# LED_Daughterboard.net
KiCad netlist of a schematic drawn in EAGLE
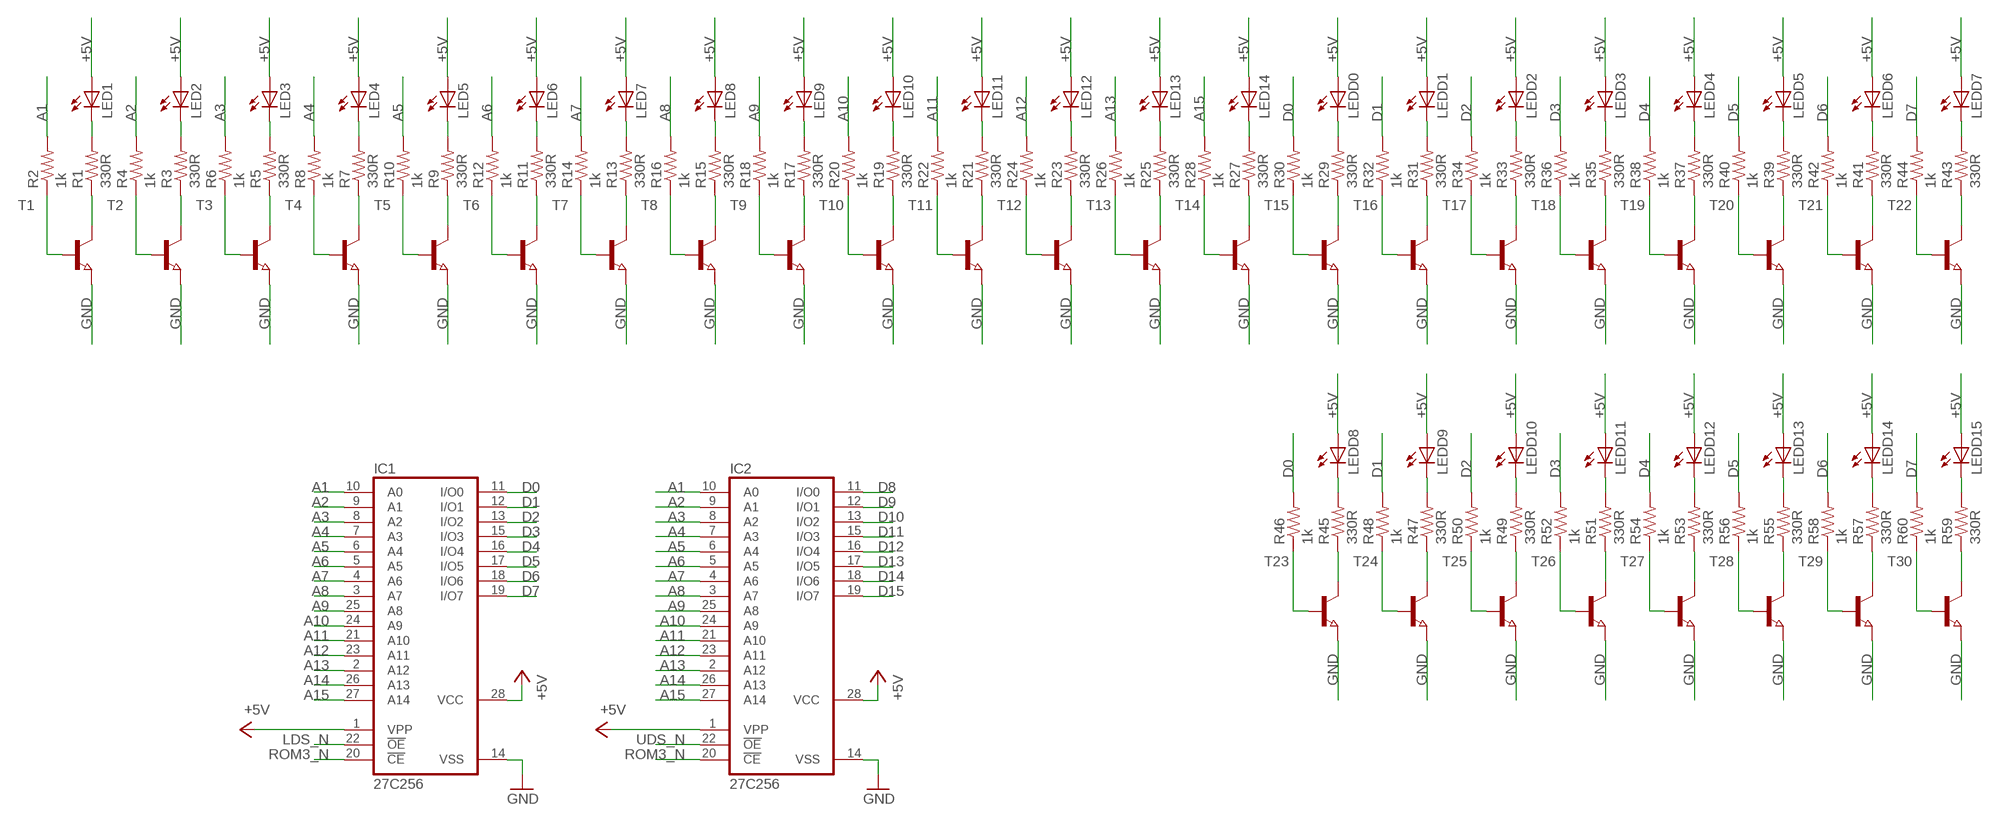
[diagram p0: schematic, sheet 1]

(export (version "E")
  (design (tool "Eeschema 10.0.6"))
  (components
    (comp (ref "IC1")
      (value "27C256")
      (footprint "eagle-import:DIL28-6")
      (libsource (lib "eagle-import") (part "27C256AG"))
    )
    (comp (ref "IC2")
      (value "27C256")
      (footprint "eagle-import:DIL28-6")
      (libsource (lib "eagle-import") (part "27C256AG"))
    )
    (comp (ref "LED1")
      (value "LEDCHIP-LED0805")
      (footprint "eagle-import:CHIP-LED0805")
      (libsource (lib "eagle-import") (part "LEDCHIP-LED0805"))
    )
    (comp (ref "LED2")
      (value "LEDCHIP-LED0805")
      (footprint "eagle-import:CHIP-LED0805")
      (libsource (lib "eagle-import") (part "LEDCHIP-LED0805"))
    )
    (comp (ref "LED3")
      (value "LEDCHIP-LED0805")
      (footprint "eagle-import:CHIP-LED0805")
      (libsource (lib "eagle-import") (part "LEDCHIP-LED0805"))
    )
    (comp (ref "LED4")
      (value "LEDCHIP-LED0805")
      (footprint "eagle-import:CHIP-LED0805")
      (libsource (lib "eagle-import") (part "LEDCHIP-LED0805"))
    )
    (comp (ref "LED5")
      (value "LEDCHIP-LED0805")
      (footprint "eagle-import:CHIP-LED0805")
      (libsource (lib "eagle-import") (part "LEDCHIP-LED0805"))
    )
    (comp (ref "LED6")
      (value "LEDCHIP-LED0805")
      (footprint "eagle-import:CHIP-LED0805")
      (libsource (lib "eagle-import") (part "LEDCHIP-LED0805"))
    )
    (comp (ref "LED7")
      (value "LEDCHIP-LED0805")
      (footprint "eagle-import:CHIP-LED0805")
      (libsource (lib "eagle-import") (part "LEDCHIP-LED0805"))
    )
    (comp (ref "LED8")
      (value "LEDCHIP-LED0805")
      (footprint "eagle-import:CHIP-LED0805")
      (libsource (lib "eagle-import") (part "LEDCHIP-LED0805"))
    )
    (comp (ref "LED9")
      (value "LEDCHIP-LED0805")
      (footprint "eagle-import:CHIP-LED0805")
      (libsource (lib "eagle-import") (part "LEDCHIP-LED0805"))
    )
    (comp (ref "LED10")
      (value "LEDCHIP-LED0805")
      (footprint "eagle-import:CHIP-LED0805")
      (libsource (lib "eagle-import") (part "LEDCHIP-LED0805"))
    )
    (comp (ref "LED11")
      (value "LEDCHIP-LED0805")
      (footprint "eagle-import:CHIP-LED0805")
      (libsource (lib "eagle-import") (part "LEDCHIP-LED0805"))
    )
    (comp (ref "LED12")
      (value "LEDCHIP-LED0805")
      (footprint "eagle-import:CHIP-LED0805")
      (libsource (lib "eagle-import") (part "LEDCHIP-LED0805"))
    )
    (comp (ref "LED13")
      (value "LEDCHIP-LED0805")
      (footprint "eagle-import:CHIP-LED0805")
      (libsource (lib "eagle-import") (part "LEDCHIP-LED0805"))
    )
    (comp (ref "LED14")
      (value "LEDCHIP-LED0805")
      (footprint "eagle-import:CHIP-LED0805")
      (libsource (lib "eagle-import") (part "LEDCHIP-LED0805"))
    )
    (comp (ref "LEDD0")
      (value "LEDCHIP-LED0805")
      (footprint "eagle-import:CHIP-LED0805")
      (libsource (lib "eagle-import") (part "LEDCHIP-LED0805"))
    )
    (comp (ref "LEDD1")
      (value "LEDCHIP-LED0805")
      (footprint "eagle-import:CHIP-LED0805")
      (libsource (lib "eagle-import") (part "LEDCHIP-LED0805"))
    )
    (comp (ref "LEDD2")
      (value "LEDCHIP-LED0805")
      (footprint "eagle-import:CHIP-LED0805")
      (libsource (lib "eagle-import") (part "LEDCHIP-LED0805"))
    )
    (comp (ref "LEDD3")
      (value "LEDCHIP-LED0805")
      (footprint "eagle-import:CHIP-LED0805")
      (libsource (lib "eagle-import") (part "LEDCHIP-LED0805"))
    )
    (comp (ref "LEDD4")
      (value "LEDCHIP-LED0805")
      (footprint "eagle-import:CHIP-LED0805")
      (libsource (lib "eagle-import") (part "LEDCHIP-LED0805"))
    )
    (comp (ref "LEDD5")
      (value "LEDCHIP-LED0805")
      (footprint "eagle-import:CHIP-LED0805")
      (libsource (lib "eagle-import") (part "LEDCHIP-LED0805"))
    )
    (comp (ref "LEDD6")
      (value "LEDCHIP-LED0805")
      (footprint "eagle-import:CHIP-LED0805")
      (libsource (lib "eagle-import") (part "LEDCHIP-LED0805"))
    )
    (comp (ref "LEDD7")
      (value "LEDCHIP-LED0805")
      (footprint "eagle-import:CHIP-LED0805")
      (libsource (lib "eagle-import") (part "LEDCHIP-LED0805"))
    )
    (comp (ref "LEDD8")
      (value "LEDCHIP-LED0805")
      (footprint "eagle-import:CHIP-LED0805")
      (libsource (lib "eagle-import") (part "LEDCHIP-LED0805"))
    )
    (comp (ref "LEDD9")
      (value "LEDCHIP-LED0805")
      (footprint "eagle-import:CHIP-LED0805")
      (libsource (lib "eagle-import") (part "LEDCHIP-LED0805"))
    )
    (comp (ref "LEDD10")
      (value "LEDCHIP-LED0805")
      (footprint "eagle-import:CHIP-LED0805")
      (libsource (lib "eagle-import") (part "LEDCHIP-LED0805"))
    )
    (comp (ref "LEDD11")
      (value "LEDCHIP-LED0805")
      (footprint "eagle-import:CHIP-LED0805")
      (libsource (lib "eagle-import") (part "LEDCHIP-LED0805"))
    )
    (comp (ref "LEDD12")
      (value "LEDCHIP-LED0805")
      (footprint "eagle-import:CHIP-LED0805")
      (libsource (lib "eagle-import") (part "LEDCHIP-LED0805"))
    )
    (comp (ref "LEDD13")
      (value "LEDCHIP-LED0805")
      (footprint "eagle-import:CHIP-LED0805")
      (libsource (lib "eagle-import") (part "LEDCHIP-LED0805"))
    )
    (comp (ref "LEDD14")
      (value "LEDCHIP-LED0805")
      (footprint "eagle-import:CHIP-LED0805")
      (libsource (lib "eagle-import") (part "LEDCHIP-LED0805"))
    )
    (comp (ref "LEDD15")
      (value "LEDCHIP-LED0805")
      (footprint "eagle-import:CHIP-LED0805")
      (libsource (lib "eagle-import") (part "LEDCHIP-LED0805"))
    )
    (comp (ref "R1")
      (value "330R")
      (footprint "eagle-import:M0805")
      (libsource (lib "eagle-import") (part "R-US_M0805"))
    )
    (comp (ref "R2")
      (value "1k")
      (footprint "eagle-import:M0805")
      (libsource (lib "eagle-import") (part "R-US_M0805"))
    )
    (comp (ref "R3")
      (value "330R")
      (footprint "eagle-import:M0805")
      (libsource (lib "eagle-import") (part "R-US_M0805"))
    )
    (comp (ref "R4")
      (value "1k")
      (footprint "eagle-import:M0805")
      (libsource (lib "eagle-import") (part "R-US_M0805"))
    )
    (comp (ref "R5")
      (value "330R")
      (footprint "eagle-import:M0805")
      (libsource (lib "eagle-import") (part "R-US_M0805"))
    )
    (comp (ref "R6")
      (value "1k")
      (footprint "eagle-import:M0805")
      (libsource (lib "eagle-import") (part "R-US_M0805"))
    )
    (comp (ref "R7")
      (value "330R")
      (footprint "eagle-import:M0805")
      (libsource (lib "eagle-import") (part "R-US_M0805"))
    )
    (comp (ref "R8")
      (value "1k")
      (footprint "eagle-import:M0805")
      (libsource (lib "eagle-import") (part "R-US_M0805"))
    )
    (comp (ref "R9")
      (value "330R")
      (footprint "eagle-import:M0805")
      (libsource (lib "eagle-import") (part "R-US_M0805"))
    )
    (comp (ref "R10")
      (value "1k")
      (footprint "eagle-import:M0805")
      (libsource (lib "eagle-import") (part "R-US_M0805"))
    )
    (comp (ref "R11")
      (value "330R")
      (footprint "eagle-import:M0805")
      (libsource (lib "eagle-import") (part "R-US_M0805"))
    )
    (comp (ref "R12")
      (value "1k")
      (footprint "eagle-import:M0805")
      (libsource (lib "eagle-import") (part "R-US_M0805"))
    )
    (comp (ref "R13")
      (value "330R")
      (footprint "eagle-import:M0805")
      (libsource (lib "eagle-import") (part "R-US_M0805"))
    )
    (comp (ref "R14")
      (value "1k")
      (footprint "eagle-import:M0805")
      (libsource (lib "eagle-import") (part "R-US_M0805"))
    )
    (comp (ref "R15")
      (value "330R")
      (footprint "eagle-import:M0805")
      (libsource (lib "eagle-import") (part "R-US_M0805"))
    )
    (comp (ref "R16")
      (value "1k")
      (footprint "eagle-import:M0805")
      (libsource (lib "eagle-import") (part "R-US_M0805"))
    )
    (comp (ref "R17")
      (value "330R")
      (footprint "eagle-import:M0805")
      (libsource (lib "eagle-import") (part "R-US_M0805"))
    )
    (comp (ref "R18")
      (value "1k")
      (footprint "eagle-import:M0805")
      (libsource (lib "eagle-import") (part "R-US_M0805"))
    )
    (comp (ref "R19")
      (value "330R")
      (footprint "eagle-import:M0805")
      (libsource (lib "eagle-import") (part "R-US_M0805"))
    )
    (comp (ref "R20")
      (value "1k")
      (footprint "eagle-import:M0805")
      (libsource (lib "eagle-import") (part "R-US_M0805"))
    )
    (comp (ref "R21")
      (value "330R")
      (footprint "eagle-import:M0805")
      (libsource (lib "eagle-import") (part "R-US_M0805"))
    )
    (comp (ref "R22")
      (value "1k")
      (footprint "eagle-import:M0805")
      (libsource (lib "eagle-import") (part "R-US_M0805"))
    )
    (comp (ref "R23")
      (value "330R")
      (footprint "eagle-import:M0805")
      (libsource (lib "eagle-import") (part "R-US_M0805"))
    )
    (comp (ref "R24")
      (value "1k")
      (footprint "eagle-import:M0805")
      (libsource (lib "eagle-import") (part "R-US_M0805"))
    )
    (comp (ref "R25")
      (value "330R")
      (footprint "eagle-import:M0805")
      (libsource (lib "eagle-import") (part "R-US_M0805"))
    )
    (comp (ref "R26")
      (value "1k")
      (footprint "eagle-import:M0805")
      (libsource (lib "eagle-import") (part "R-US_M0805"))
    )
    (comp (ref "R27")
      (value "330R")
      (footprint "eagle-import:M0805")
      (libsource (lib "eagle-import") (part "R-US_M0805"))
    )
    (comp (ref "R28")
      (value "1k")
      (footprint "eagle-import:M0805")
      (libsource (lib "eagle-import") (part "R-US_M0805"))
    )
    (comp (ref "R29")
      (value "330R")
      (footprint "eagle-import:M0805")
      (libsource (lib "eagle-import") (part "R-US_M0805"))
    )
    (comp (ref "R30")
      (value "1k")
      (footprint "eagle-import:M0805")
      (libsource (lib "eagle-import") (part "R-US_M0805"))
    )
    (comp (ref "R31")
      (value "330R")
      (footprint "eagle-import:M0805")
      (libsource (lib "eagle-import") (part "R-US_M0805"))
    )
    (comp (ref "R32")
      (value "1k")
      (footprint "eagle-import:M0805")
      (libsource (lib "eagle-import") (part "R-US_M0805"))
    )
    (comp (ref "R33")
      (value "330R")
      (footprint "eagle-import:M0805")
      (libsource (lib "eagle-import") (part "R-US_M0805"))
    )
    (comp (ref "R34")
      (value "1k")
      (footprint "eagle-import:M0805")
      (libsource (lib "eagle-import") (part "R-US_M0805"))
    )
    (comp (ref "R35")
      (value "330R")
      (footprint "eagle-import:M0805")
      (libsource (lib "eagle-import") (part "R-US_M0805"))
    )
    (comp (ref "R36")
      (value "1k")
      (footprint "eagle-import:M0805")
      (libsource (lib "eagle-import") (part "R-US_M0805"))
    )
    (comp (ref "R37")
      (value "330R")
      (footprint "eagle-import:M0805")
      (libsource (lib "eagle-import") (part "R-US_M0805"))
    )
    (comp (ref "R38")
      (value "1k")
      (footprint "eagle-import:M0805")
      (libsource (lib "eagle-import") (part "R-US_M0805"))
    )
    (comp (ref "R39")
      (value "330R")
      (footprint "eagle-import:M0805")
      (libsource (lib "eagle-import") (part "R-US_M0805"))
    )
    (comp (ref "R40")
      (value "1k")
      (footprint "eagle-import:M0805")
      (libsource (lib "eagle-import") (part "R-US_M0805"))
    )
    (comp (ref "R41")
      (value "330R")
      (footprint "eagle-import:M0805")
      (libsource (lib "eagle-import") (part "R-US_M0805"))
    )
    (comp (ref "R42")
      (value "1k")
      (footprint "eagle-import:M0805")
      (libsource (lib "eagle-import") (part "R-US_M0805"))
    )
    (comp (ref "R43")
      (value "330R")
      (footprint "eagle-import:M0805")
      (libsource (lib "eagle-import") (part "R-US_M0805"))
    )
    (comp (ref "R44")
      (value "1k")
      (footprint "eagle-import:M0805")
      (libsource (lib "eagle-import") (part "R-US_M0805"))
    )
    (comp (ref "R45")
      (value "330R")
      (footprint "eagle-import:M0805")
      (libsource (lib "eagle-import") (part "R-US_M0805"))
    )
    (comp (ref "R46")
      (value "1k")
      (footprint "eagle-import:M0805")
      (libsource (lib "eagle-import") (part "R-US_M0805"))
    )
    (comp (ref "R47")
      (value "330R")
      (footprint "eagle-import:M0805")
      (libsource (lib "eagle-import") (part "R-US_M0805"))
    )
    (comp (ref "R48")
      (value "1k")
      (footprint "eagle-import:M0805")
      (libsource (lib "eagle-import") (part "R-US_M0805"))
    )
    (comp (ref "R49")
      (value "330R")
      (footprint "eagle-import:M0805")
      (libsource (lib "eagle-import") (part "R-US_M0805"))
    )
    (comp (ref "R50")
      (value "1k")
      (footprint "eagle-import:M0805")
      (libsource (lib "eagle-import") (part "R-US_M0805"))
    )
    (comp (ref "R51")
      (value "330R")
      (footprint "eagle-import:M0805")
      (libsource (lib "eagle-import") (part "R-US_M0805"))
    )
    (comp (ref "R52")
      (value "1k")
      (footprint "eagle-import:M0805")
      (libsource (lib "eagle-import") (part "R-US_M0805"))
    )
    (comp (ref "R53")
      (value "330R")
      (footprint "eagle-import:M0805")
      (libsource (lib "eagle-import") (part "R-US_M0805"))
    )
    (comp (ref "R54")
      (value "1k")
      (footprint "eagle-import:M0805")
      (libsource (lib "eagle-import") (part "R-US_M0805"))
    )
    (comp (ref "R55")
      (value "330R")
      (footprint "eagle-import:M0805")
      (libsource (lib "eagle-import") (part "R-US_M0805"))
    )
    (comp (ref "R56")
      (value "1k")
      (footprint "eagle-import:M0805")
      (libsource (lib "eagle-import") (part "R-US_M0805"))
    )
    (comp (ref "R57")
      (value "330R")
      (footprint "eagle-import:M0805")
      (libsource (lib "eagle-import") (part "R-US_M0805"))
    )
    (comp (ref "R58")
      (value "1k")
      (footprint "eagle-import:M0805")
      (libsource (lib "eagle-import") (part "R-US_M0805"))
    )
    (comp (ref "R59")
      (value "330R")
      (footprint "eagle-import:M0805")
      (libsource (lib "eagle-import") (part "R-US_M0805"))
    )
    (comp (ref "R60")
      (value "1k")
      (footprint "eagle-import:M0805")
      (libsource (lib "eagle-import") (part "R-US_M0805"))
    )
    (comp (ref "T1")
      (value "NPN-TRANSISTOR_SOT23")
      (footprint "eagle-import:SOT23")
      (libsource (lib "eagle-import") (part "NPN-TRANSISTOR_SOT23"))
    )
    (comp (ref "T2")
      (value "NPN-TRANSISTOR_SOT23")
      (footprint "eagle-import:SOT23")
      (libsource (lib "eagle-import") (part "NPN-TRANSISTOR_SOT23"))
    )
    (comp (ref "T3")
      (value "NPN-TRANSISTOR_SOT23")
      (footprint "eagle-import:SOT23")
      (libsource (lib "eagle-import") (part "NPN-TRANSISTOR_SOT23"))
    )
    (comp (ref "T4")
      (value "NPN-TRANSISTOR_SOT23")
      (footprint "eagle-import:SOT23")
      (libsource (lib "eagle-import") (part "NPN-TRANSISTOR_SOT23"))
    )
    (comp (ref "T5")
      (value "NPN-TRANSISTOR_SOT23")
      (footprint "eagle-import:SOT23")
      (libsource (lib "eagle-import") (part "NPN-TRANSISTOR_SOT23"))
    )
    (comp (ref "T6")
      (value "NPN-TRANSISTOR_SOT23")
      (footprint "eagle-import:SOT23")
      (libsource (lib "eagle-import") (part "NPN-TRANSISTOR_SOT23"))
    )
    (comp (ref "T7")
      (value "NPN-TRANSISTOR_SOT23")
      (footprint "eagle-import:SOT23")
      (libsource (lib "eagle-import") (part "NPN-TRANSISTOR_SOT23"))
    )
    (comp (ref "T8")
      (value "NPN-TRANSISTOR_SOT23")
      (footprint "eagle-import:SOT23")
      (libsource (lib "eagle-import") (part "NPN-TRANSISTOR_SOT23"))
    )
    (comp (ref "T9")
      (value "NPN-TRANSISTOR_SOT23")
      (footprint "eagle-import:SOT23")
      (libsource (lib "eagle-import") (part "NPN-TRANSISTOR_SOT23"))
    )
    (comp (ref "T10")
      (value "NPN-TRANSISTOR_SOT23")
      (footprint "eagle-import:SOT23")
      (libsource (lib "eagle-import") (part "NPN-TRANSISTOR_SOT23"))
    )
    (comp (ref "T11")
      (value "NPN-TRANSISTOR_SOT23")
      (footprint "eagle-import:SOT23")
      (libsource (lib "eagle-import") (part "NPN-TRANSISTOR_SOT23"))
    )
    (comp (ref "T12")
      (value "NPN-TRANSISTOR_SOT23")
      (footprint "eagle-import:SOT23")
      (libsource (lib "eagle-import") (part "NPN-TRANSISTOR_SOT23"))
    )
    (comp (ref "T13")
      (value "NPN-TRANSISTOR_SOT23")
      (footprint "eagle-import:SOT23")
      (libsource (lib "eagle-import") (part "NPN-TRANSISTOR_SOT23"))
    )
    (comp (ref "T14")
      (value "NPN-TRANSISTOR_SOT23")
      (footprint "eagle-import:SOT23")
      (libsource (lib "eagle-import") (part "NPN-TRANSISTOR_SOT23"))
    )
    (comp (ref "T15")
      (value "NPN-TRANSISTOR_SOT23")
      (footprint "eagle-import:SOT23")
      (libsource (lib "eagle-import") (part "NPN-TRANSISTOR_SOT23"))
    )
    (comp (ref "T16")
      (value "NPN-TRANSISTOR_SOT23")
      (footprint "eagle-import:SOT23")
      (libsource (lib "eagle-import") (part "NPN-TRANSISTOR_SOT23"))
    )
    (comp (ref "T17")
      (value "NPN-TRANSISTOR_SOT23")
      (footprint "eagle-import:SOT23")
      (libsource (lib "eagle-import") (part "NPN-TRANSISTOR_SOT23"))
    )
    (comp (ref "T18")
      (value "NPN-TRANSISTOR_SOT23")
      (footprint "eagle-import:SOT23")
      (libsource (lib "eagle-import") (part "NPN-TRANSISTOR_SOT23"))
    )
    (comp (ref "T19")
      (value "NPN-TRANSISTOR_SOT23")
      (footprint "eagle-import:SOT23")
      (libsource (lib "eagle-import") (part "NPN-TRANSISTOR_SOT23"))
    )
    (comp (ref "T20")
      (value "NPN-TRANSISTOR_SOT23")
      (footprint "eagle-import:SOT23")
      (libsource (lib "eagle-import") (part "NPN-TRANSISTOR_SOT23"))
    )
    (comp (ref "T21")
      (value "NPN-TRANSISTOR_SOT23")
      (footprint "eagle-import:SOT23")
      (libsource (lib "eagle-import") (part "NPN-TRANSISTOR_SOT23"))
    )
    (comp (ref "T22")
      (value "NPN-TRANSISTOR_SOT23")
      (footprint "eagle-import:SOT23")
      (libsource (lib "eagle-import") (part "NPN-TRANSISTOR_SOT23"))
    )
    (comp (ref "T23")
      (value "NPN-TRANSISTOR_SOT23")
      (footprint "eagle-import:SOT23")
      (libsource (lib "eagle-import") (part "NPN-TRANSISTOR_SOT23"))
    )
    (comp (ref "T24")
      (value "NPN-TRANSISTOR_SOT23")
      (footprint "eagle-import:SOT23")
      (libsource (lib "eagle-import") (part "NPN-TRANSISTOR_SOT23"))
    )
    (comp (ref "T25")
      (value "NPN-TRANSISTOR_SOT23")
      (footprint "eagle-import:SOT23")
      (libsource (lib "eagle-import") (part "NPN-TRANSISTOR_SOT23"))
    )
    (comp (ref "T26")
      (value "NPN-TRANSISTOR_SOT23")
      (footprint "eagle-import:SOT23")
      (libsource (lib "eagle-import") (part "NPN-TRANSISTOR_SOT23"))
    )
    (comp (ref "T27")
      (value "NPN-TRANSISTOR_SOT23")
      (footprint "eagle-import:SOT23")
      (libsource (lib "eagle-import") (part "NPN-TRANSISTOR_SOT23"))
    )
    (comp (ref "T28")
      (value "NPN-TRANSISTOR_SOT23")
      (footprint "eagle-import:SOT23")
      (libsource (lib "eagle-import") (part "NPN-TRANSISTOR_SOT23"))
    )
    (comp (ref "T29")
      (value "NPN-TRANSISTOR_SOT23")
      (footprint "eagle-import:SOT23")
      (libsource (lib "eagle-import") (part "NPN-TRANSISTOR_SOT23"))
    )
    (comp (ref "T30")
      (value "NPN-TRANSISTOR_SOT23")
      (footprint "eagle-import:SOT23")
      (libsource (lib "eagle-import") (part "NPN-TRANSISTOR_SOT23"))
    )
  )
  (nets
    (net (code "1") (name "+5V") (class "Default")
      (node (ref "IC1") (pin "1") (pinfunction "VPP_1") (pintype "input"))
      (node (ref "IC1") (pin "28") (pinfunction "VCC_28") (pintype "power_in"))
      (node (ref "IC2") (pin "1") (pinfunction "VPP_1") (pintype "input"))
      (node (ref "IC2") (pin "28") (pinfunction "VCC_28") (pintype "power_in"))
      (node (ref "LED1") (pin "A") (pinfunction "A_A") (pintype "passive"))
      (node (ref "LED10") (pin "A") (pinfunction "A_A") (pintype "passive"))
      (node (ref "LED11") (pin "A") (pinfunction "A_A") (pintype "passive"))
      (node (ref "LED12") (pin "A") (pinfunction "A_A") (pintype "passive"))
      (node (ref "LED13") (pin "A") (pinfunction "A_A") (pintype "passive"))
      (node (ref "LED14") (pin "A") (pinfunction "A_A") (pintype "passive"))
      (node (ref "LED2") (pin "A") (pinfunction "A_A") (pintype "passive"))
      (node (ref "LED3") (pin "A") (pinfunction "A_A") (pintype "passive"))
      (node (ref "LED4") (pin "A") (pinfunction "A_A") (pintype "passive"))
      (node (ref "LED5") (pin "A") (pinfunction "A_A") (pintype "passive"))
      (node (ref "LED6") (pin "A") (pinfunction "A_A") (pintype "passive"))
      (node (ref "LED7") (pin "A") (pinfunction "A_A") (pintype "passive"))
      (node (ref "LED8") (pin "A") (pinfunction "A_A") (pintype "passive"))
      (node (ref "LED9") (pin "A") (pinfunction "A_A") (pintype "passive"))
      (node (ref "LEDD0") (pin "A") (pinfunction "A_A") (pintype "passive"))
      (node (ref "LEDD1") (pin "A") (pinfunction "A_A") (pintype "passive"))
      (node (ref "LEDD10") (pin "A") (pinfunction "A_A") (pintype "passive"))
      (node (ref "LEDD11") (pin "A") (pinfunction "A_A") (pintype "passive"))
      (node (ref "LEDD12") (pin "A") (pinfunction "A_A") (pintype "passive"))
      (node (ref "LEDD13") (pin "A") (pinfunction "A_A") (pintype "passive"))
      (node (ref "LEDD14") (pin "A") (pinfunction "A_A") (pintype "passive"))
      (node (ref "LEDD15") (pin "A") (pinfunction "A_A") (pintype "passive"))
      (node (ref "LEDD2") (pin "A") (pinfunction "A_A") (pintype "passive"))
      (node (ref "LEDD3") (pin "A") (pinfunction "A_A") (pintype "passive"))
      (node (ref "LEDD4") (pin "A") (pinfunction "A_A") (pintype "passive"))
      (node (ref "LEDD5") (pin "A") (pinfunction "A_A") (pintype "passive"))
      (node (ref "LEDD6") (pin "A") (pinfunction "A_A") (pintype "passive"))
      (node (ref "LEDD7") (pin "A") (pinfunction "A_A") (pintype "passive"))
      (node (ref "LEDD8") (pin "A") (pinfunction "A_A") (pintype "passive"))
      (node (ref "LEDD9") (pin "A") (pinfunction "A_A") (pintype "passive"))
    )
    (net (code "2") (name "/A1") (class "Default")
      (node (ref "IC1") (pin "10") (pinfunction "A0_10") (pintype "input"))
      (node (ref "IC2") (pin "10") (pinfunction "A0_10") (pintype "input"))
      (node (ref "R2") (pin "2") (pinfunction "2_2") (pintype "passive"))
    )
    (net (code "3") (name "/A2") (class "Default")
      (node (ref "IC1") (pin "9") (pinfunction "A1_9") (pintype "input"))
      (node (ref "IC2") (pin "9") (pinfunction "A1_9") (pintype "input"))
      (node (ref "R4") (pin "2") (pinfunction "2_2") (pintype "passive"))
    )
    (net (code "4") (name "/A3") (class "Default")
      (node (ref "IC1") (pin "8") (pinfunction "A2_8") (pintype "input"))
      (node (ref "IC2") (pin "8") (pinfunction "A2_8") (pintype "input"))
      (node (ref "R6") (pin "2") (pinfunction "2_2") (pintype "passive"))
    )
    (net (code "5") (name "/A4") (class "Default")
      (node (ref "IC1") (pin "7") (pinfunction "A3_7") (pintype "input"))
      (node (ref "IC2") (pin "7") (pinfunction "A3_7") (pintype "input"))
      (node (ref "R8") (pin "2") (pinfunction "2_2") (pintype "passive"))
    )
    (net (code "6") (name "/A5") (class "Default")
      (node (ref "IC1") (pin "6") (pinfunction "A4_6") (pintype "input"))
      (node (ref "IC2") (pin "6") (pinfunction "A4_6") (pintype "input"))
      (node (ref "R10") (pin "2") (pinfunction "2_2") (pintype "passive"))
    )
    (net (code "7") (name "/A6") (class "Default")
      (node (ref "IC1") (pin "5") (pinfunction "A5_5") (pintype "input"))
      (node (ref "IC2") (pin "5") (pinfunction "A5_5") (pintype "input"))
      (node (ref "R12") (pin "2") (pinfunction "2_2") (pintype "passive"))
    )
    (net (code "8") (name "/A7") (class "Default")
      (node (ref "IC1") (pin "4") (pinfunction "A6_4") (pintype "input"))
      (node (ref "IC2") (pin "4") (pinfunction "A6_4") (pintype "input"))
      (node (ref "R14") (pin "2") (pinfunction "2_2") (pintype "passive"))
    )
    (net (code "9") (name "/A8") (class "Default")
      (node (ref "IC1") (pin "3") (pinfunction "A7_3") (pintype "input"))
      (node (ref "IC2") (pin "3") (pinfunction "A7_3") (pintype "input"))
      (node (ref "R16") (pin "2") (pinfunction "2_2") (pintype "passive"))
    )
    (net (code "10") (name "/A9") (class "Default")
      (node (ref "IC1") (pin "25") (pinfunction "A8_25") (pintype "input"))
      (node (ref "IC2") (pin "25") (pinfunction "A8_25") (pintype "input"))
      (node (ref "R18") (pin "2") (pinfunction "2_2") (pintype "passive"))
    )
    (net (code "11") (name "/A10") (class "Default")
      (node (ref "IC1") (pin "24") (pinfunction "A9_24") (pintype "input"))
      (node (ref "IC2") (pin "24") (pinfunction "A9_24") (pintype "input"))
      (node (ref "R20") (pin "2") (pinfunction "2_2") (pintype "passive"))
    )
    (net (code "12") (name "/A11") (class "Default")
      (node (ref "IC1") (pin "21") (pinfunction "A10_21") (pintype "input"))
      (node (ref "IC2") (pin "21") (pinfunction "A10_21") (pintype "input"))
      (node (ref "R22") (pin "2") (pinfunction "2_2") (pintype "passive"))
    )
    (net (code "13") (name "/A12") (class "Default")
      (node (ref "IC1") (pin "23") (pinfunction "A11_23") (pintype "input"))
      (node (ref "IC2") (pin "23") (pinfunction "A11_23") (pintype "input"))
      (node (ref "R24") (pin "2") (pinfunction "2_2") (pintype "passive"))
    )
    (net (code "14") (name "/A13") (class "Default")
      (node (ref "IC1") (pin "2") (pinfunction "A12_2") (pintype "input"))
      (node (ref "IC2") (pin "2") (pinfunction "A12_2") (pintype "input"))
      (node (ref "R26") (pin "2") (pinfunction "2_2") (pintype "passive"))
    )
    (net (code "15") (name "/A14") (class "Default")
      (node (ref "IC1") (pin "26") (pinfunction "A13_26") (pintype "input"))
      (node (ref "IC2") (pin "26") (pinfunction "A13_26") (pintype "input"))
    )
    (net (code "16") (name "/A15") (class "Default")
      (node (ref "IC1") (pin "27") (pinfunction "A14_27") (pintype "input"))
      (node (ref "IC2") (pin "27") (pinfunction "A14_27") (pintype "input"))
      (node (ref "R28") (pin "2") (pinfunction "2_2") (pintype "passive"))
    )
    (net (code "17") (name "/D0") (class "Default")
      (node (ref "IC1") (pin "11") (pinfunction "I/O0_11") (pintype "tri_state"))
      (node (ref "R30") (pin "2") (pinfunction "2_2") (pintype "passive"))
      (node (ref "R46") (pin "2") (pinfunction "2_2") (pintype "passive"))
    )
    (net (code "18") (name "/D1") (class "Default")
      (node (ref "IC1") (pin "12") (pinfunction "I/O1_12") (pintype "tri_state"))
      (node (ref "R32") (pin "2") (pinfunction "2_2") (pintype "passive"))
      (node (ref "R48") (pin "2") (pinfunction "2_2") (pintype "passive"))
    )
    (net (code "19") (name "/D2") (class "Default")
      (node (ref "IC1") (pin "13") (pinfunction "I/O2_13") (pintype "tri_state"))
      (node (ref "R34") (pin "2") (pinfunction "2_2") (pintype "passive"))
      (node (ref "R50") (pin "2") (pinfunction "2_2") (pintype "passive"))
    )
    (net (code "20") (name "/D3") (class "Default")
      (node (ref "IC1") (pin "15") (pinfunction "I/O3_15") (pintype "tri_state"))
      (node (ref "R36") (pin "2") (pinfunction "2_2") (pintype "passive"))
      (node (ref "R52") (pin "2") (pinfunction "2_2") (pintype "passive"))
    )
    (net (code "21") (name "/D4") (class "Default")
      (node (ref "IC1") (pin "16") (pinfunction "I/O4_16") (pintype "tri_state"))
      (node (ref "R38") (pin "2") (pinfunction "2_2") (pintype "passive"))
      (node (ref "R54") (pin "2") (pinfunction "2_2") (pintype "passive"))
    )
    (net (code "22") (name "/D5") (class "Default")
      (node (ref "IC1") (pin "17") (pinfunction "I/O5_17") (pintype "tri_state"))
      (node (ref "R40") (pin "2") (pinfunction "2_2") (pintype "passive"))
      (node (ref "R56") (pin "2") (pinfunction "2_2") (pintype "passive"))
    )
    (net (code "23") (name "/D6") (class "Default")
      (node (ref "IC1") (pin "18") (pinfunction "I/O6_18") (pintype "tri_state"))
      (node (ref "R42") (pin "2") (pinfunction "2_2") (pintype "passive"))
      (node (ref "R58") (pin "2") (pinfunction "2_2") (pintype "passive"))
    )
    (net (code "24") (name "/D7") (class "Default")
      (node (ref "IC1") (pin "19") (pinfunction "I/O7_19") (pintype "tri_state"))
      (node (ref "R44") (pin "2") (pinfunction "2_2") (pintype "passive"))
      (node (ref "R60") (pin "2") (pinfunction "2_2") (pintype "passive"))
    )
    (net (code "25") (name "/D8") (class "Default")
      (node (ref "IC2") (pin "11") (pinfunction "I/O0_11") (pintype "tri_state"))
    )
    (net (code "26") (name "/D9") (class "Default")
      (node (ref "IC2") (pin "12") (pinfunction "I/O1_12") (pintype "tri_state"))
    )
    (net (code "27") (name "/D10") (class "Default")
      (node (ref "IC2") (pin "13") (pinfunction "I/O2_13") (pintype "tri_state"))
    )
    (net (code "28") (name "/D11") (class "Default")
      (node (ref "IC2") (pin "15") (pinfunction "I/O3_15") (pintype "tri_state"))
    )
    (net (code "29") (name "/D12") (class "Default")
      (node (ref "IC2") (pin "16") (pinfunction "I/O4_16") (pintype "tri_state"))
    )
    (net (code "30") (name "/D13") (class "Default")
      (node (ref "IC2") (pin "17") (pinfunction "I/O5_17") (pintype "tri_state"))
    )
    (net (code "31") (name "/D14") (class "Default")
      (node (ref "IC2") (pin "18") (pinfunction "I/O6_18") (pintype "tri_state"))
    )
    (net (code "32") (name "/D15") (class "Default")
      (node (ref "IC2") (pin "19") (pinfunction "I/O7_19") (pintype "tri_state"))
    )
    (net (code "33") (name "/LDS_N") (class "Default")
      (node (ref "IC1") (pin "22") (pinfunction "~{OE}_22") (pintype "input"))
    )
    (net (code "34") (name "/ROM3_N") (class "Default")
      (node (ref "IC1") (pin "20") (pinfunction "~{CE}_20") (pintype "input"))
      (node (ref "IC2") (pin "20") (pinfunction "~{CE}_20") (pintype "input"))
    )
    (net (code "35") (name "/UDS_N") (class "Default")
      (node (ref "IC2") (pin "22") (pinfunction "~{OE}_22") (pintype "input"))
    )
    (net (code "36") (name "GND") (class "Default")
      (node (ref "IC1") (pin "14") (pinfunction "VSS_14") (pintype "power_in"))
      (node (ref "IC2") (pin "14") (pinfunction "VSS_14") (pintype "power_in"))
      (node (ref "T1") (pin "2") (pinfunction "E_2") (pintype "passive"))
      (node (ref "T10") (pin "2") (pinfunction "E_2") (pintype "passive"))
      (node (ref "T11") (pin "2") (pinfunction "E_2") (pintype "passive"))
      (node (ref "T12") (pin "2") (pinfunction "E_2") (pintype "passive"))
      (node (ref "T13") (pin "2") (pinfunction "E_2") (pintype "passive"))
      (node (ref "T14") (pin "2") (pinfunction "E_2") (pintype "passive"))
      (node (ref "T15") (pin "2") (pinfunction "E_2") (pintype "passive"))
      (node (ref "T16") (pin "2") (pinfunction "E_2") (pintype "passive"))
      (node (ref "T17") (pin "2") (pinfunction "E_2") (pintype "passive"))
      (node (ref "T18") (pin "2") (pinfunction "E_2") (pintype "passive"))
      (node (ref "T19") (pin "2") (pinfunction "E_2") (pintype "passive"))
      (node (ref "T2") (pin "2") (pinfunction "E_2") (pintype "passive"))
      (node (ref "T20") (pin "2") (pinfunction "E_2") (pintype "passive"))
      (node (ref "T21") (pin "2") (pinfunction "E_2") (pintype "passive"))
      (node (ref "T22") (pin "2") (pinfunction "E_2") (pintype "passive"))
      (node (ref "T23") (pin "2") (pinfunction "E_2") (pintype "passive"))
      (node (ref "T24") (pin "2") (pinfunction "E_2") (pintype "passive"))
      (node (ref "T25") (pin "2") (pinfunction "E_2") (pintype "passive"))
      (node (ref "T26") (pin "2") (pinfunction "E_2") (pintype "passive"))
      (node (ref "T27") (pin "2") (pinfunction "E_2") (pintype "passive"))
      (node (ref "T28") (pin "2") (pinfunction "E_2") (pintype "passive"))
      (node (ref "T29") (pin "2") (pinfunction "E_2") (pintype "passive"))
      (node (ref "T3") (pin "2") (pinfunction "E_2") (pintype "passive"))
      (node (ref "T30") (pin "2") (pinfunction "E_2") (pintype "passive"))
      (node (ref "T4") (pin "2") (pinfunction "E_2") (pintype "passive"))
      (node (ref "T5") (pin "2") (pinfunction "E_2") (pintype "passive"))
      (node (ref "T6") (pin "2") (pinfunction "E_2") (pintype "passive"))
      (node (ref "T7") (pin "2") (pinfunction "E_2") (pintype "passive"))
      (node (ref "T8") (pin "2") (pinfunction "E_2") (pintype "passive"))
      (node (ref "T9") (pin "2") (pinfunction "E_2") (pintype "passive"))
    )
    (net (code "37") (name "Net-(LED1-PadC)") (class "Default")
      (node (ref "LED1") (pin "C") (pinfunction "C_C") (pintype "passive"))
      (node (ref "R1") (pin "2") (pinfunction "2_2") (pintype "passive"))
    )
    (net (code "38") (name "Net-(LED2-PadC)") (class "Default")
      (node (ref "LED2") (pin "C") (pinfunction "C_C") (pintype "passive"))
      (node (ref "R3") (pin "2") (pinfunction "2_2") (pintype "passive"))
    )
    (net (code "39") (name "Net-(LED3-PadC)") (class "Default")
      (node (ref "LED3") (pin "C") (pinfunction "C_C") (pintype "passive"))
      (node (ref "R5") (pin "2") (pinfunction "2_2") (pintype "passive"))
    )
    (net (code "40") (name "Net-(LED4-PadC)") (class "Default")
      (node (ref "LED4") (pin "C") (pinfunction "C_C") (pintype "passive"))
      (node (ref "R7") (pin "2") (pinfunction "2_2") (pintype "passive"))
    )
    (net (code "41") (name "Net-(LED5-PadC)") (class "Default")
      (node (ref "LED5") (pin "C") (pinfunction "C_C") (pintype "passive"))
      (node (ref "R9") (pin "2") (pinfunction "2_2") (pintype "passive"))
    )
    (net (code "42") (name "Net-(LED6-PadC)") (class "Default")
      (node (ref "LED6") (pin "C") (pinfunction "C_C") (pintype "passive"))
      (node (ref "R11") (pin "2") (pinfunction "2_2") (pintype "passive"))
    )
    (net (code "43") (name "Net-(LED7-PadC)") (class "Default")
      (node (ref "LED7") (pin "C") (pinfunction "C_C") (pintype "passive"))
      (node (ref "R13") (pin "2") (pinfunction "2_2") (pintype "passive"))
    )
    (net (code "44") (name "Net-(LED8-PadC)") (class "Default")
      (node (ref "LED8") (pin "C") (pinfunction "C_C") (pintype "passive"))
      (node (ref "R15") (pin "2") (pinfunction "2_2") (pintype "passive"))
    )
    (net (code "45") (name "Net-(LED9-PadC)") (class "Default")
      (node (ref "LED9") (pin "C") (pinfunction "C_C") (pintype "passive"))
      (node (ref "R17") (pin "2") (pinfunction "2_2") (pintype "passive"))
    )
    (net (code "46") (name "Net-(LED10-PadC)") (class "Default")
      (node (ref "LED10") (pin "C") (pinfunction "C_C") (pintype "passive"))
      (node (ref "R19") (pin "2") (pinfunction "2_2") (pintype "passive"))
    )
    (net (code "47") (name "Net-(LED11-PadC)") (class "Default")
      (node (ref "LED11") (pin "C") (pinfunction "C_C") (pintype "passive"))
      (node (ref "R21") (pin "2") (pinfunction "2_2") (pintype "passive"))
    )
    (net (code "48") (name "Net-(LED12-PadC)") (class "Default")
      (node (ref "LED12") (pin "C") (pinfunction "C_C") (pintype "passive"))
      (node (ref "R23") (pin "2") (pinfunction "2_2") (pintype "passive"))
    )
    (net (code "49") (name "Net-(LED13-PadC)") (class "Default")
      (node (ref "LED13") (pin "C") (pinfunction "C_C") (pintype "passive"))
      (node (ref "R25") (pin "2") (pinfunction "2_2") (pintype "passive"))
    )
    (net (code "50") (name "Net-(LED14-PadC)") (class "Default")
      (node (ref "LED14") (pin "C") (pinfunction "C_C") (pintype "passive"))
      (node (ref "R27") (pin "2") (pinfunction "2_2") (pintype "passive"))
    )
    (net (code "51") (name "Net-(LEDD0-PadC)") (class "Default")
      (node (ref "LEDD0") (pin "C") (pinfunction "C_C") (pintype "passive"))
      (node (ref "R29") (pin "2") (pinfunction "2_2") (pintype "passive"))
    )
    (net (code "52") (name "Net-(LEDD1-PadC)") (class "Default")
      (node (ref "LEDD1") (pin "C") (pinfunction "C_C") (pintype "passive"))
      (node (ref "R31") (pin "2") (pinfunction "2_2") (pintype "passive"))
    )
    (net (code "53") (name "Net-(LEDD2-PadC)") (class "Default")
      (node (ref "LEDD2") (pin "C") (pinfunction "C_C") (pintype "passive"))
      (node (ref "R33") (pin "2") (pinfunction "2_2") (pintype "passive"))
    )
    (net (code "54") (name "Net-(LEDD3-PadC)") (class "Default")
      (node (ref "LEDD3") (pin "C") (pinfunction "C_C") (pintype "passive"))
      (node (ref "R35") (pin "2") (pinfunction "2_2") (pintype "passive"))
    )
    (net (code "55") (name "Net-(LEDD4-PadC)") (class "Default")
      (node (ref "LEDD4") (pin "C") (pinfunction "C_C") (pintype "passive"))
      (node (ref "R37") (pin "2") (pinfunction "2_2") (pintype "passive"))
    )
    (net (code "56") (name "Net-(LEDD5-PadC)") (class "Default")
      (node (ref "LEDD5") (pin "C") (pinfunction "C_C") (pintype "passive"))
      (node (ref "R39") (pin "2") (pinfunction "2_2") (pintype "passive"))
    )
    (net (code "57") (name "Net-(LEDD6-PadC)") (class "Default")
      (node (ref "LEDD6") (pin "C") (pinfunction "C_C") (pintype "passive"))
      (node (ref "R41") (pin "2") (pinfunction "2_2") (pintype "passive"))
    )
    (net (code "58") (name "Net-(LEDD7-PadC)") (class "Default")
      (node (ref "LEDD7") (pin "C") (pinfunction "C_C") (pintype "passive"))
      (node (ref "R43") (pin "2") (pinfunction "2_2") (pintype "passive"))
    )
    (net (code "59") (name "Net-(LEDD8-PadC)") (class "Default")
      (node (ref "LEDD8") (pin "C") (pinfunction "C_C") (pintype "passive"))
      (node (ref "R45") (pin "2") (pinfunction "2_2") (pintype "passive"))
    )
    (net (code "60") (name "Net-(LEDD9-PadC)") (class "Default")
      (node (ref "LEDD9") (pin "C") (pinfunction "C_C") (pintype "passive"))
      (node (ref "R47") (pin "2") (pinfunction "2_2") (pintype "passive"))
    )
    (net (code "61") (name "Net-(LEDD10-PadC)") (class "Default")
      (node (ref "LEDD10") (pin "C") (pinfunction "C_C") (pintype "passive"))
      (node (ref "R49") (pin "2") (pinfunction "2_2") (pintype "passive"))
    )
    (net (code "62") (name "Net-(LEDD11-PadC)") (class "Default")
      (node (ref "LEDD11") (pin "C") (pinfunction "C_C") (pintype "passive"))
      (node (ref "R51") (pin "2") (pinfunction "2_2") (pintype "passive"))
    )
    (net (code "63") (name "Net-(LEDD12-PadC)") (class "Default")
      (node (ref "LEDD12") (pin "C") (pinfunction "C_C") (pintype "passive"))
      (node (ref "R53") (pin "2") (pinfunction "2_2") (pintype "passive"))
    )
    (net (code "64") (name "Net-(LEDD13-PadC)") (class "Default")
      (node (ref "LEDD13") (pin "C") (pinfunction "C_C") (pintype "passive"))
      (node (ref "R55") (pin "2") (pinfunction "2_2") (pintype "passive"))
    )
    (net (code "65") (name "Net-(LEDD14-PadC)") (class "Default")
      (node (ref "LEDD14") (pin "C") (pinfunction "C_C") (pintype "passive"))
      (node (ref "R57") (pin "2") (pinfunction "2_2") (pintype "passive"))
    )
    (net (code "66") (name "Net-(LEDD15-PadC)") (class "Default")
      (node (ref "LEDD15") (pin "C") (pinfunction "C_C") (pintype "passive"))
      (node (ref "R59") (pin "2") (pinfunction "2_2") (pintype "passive"))
    )
    (net (code "67") (name "Net-(T1-B)") (class "Default")
      (node (ref "R2") (pin "1") (pinfunction "1_1") (pintype "passive"))
      (node (ref "T1") (pin "1") (pinfunction "B_1") (pintype "passive"))
    )
    (net (code "68") (name "Net-(T1-C)") (class "Default")
      (node (ref "R1") (pin "1") (pinfunction "1_1") (pintype "passive"))
      (node (ref "T1") (pin "3") (pinfunction "C_3") (pintype "passive"))
    )
    (net (code "69") (name "Net-(T2-B)") (class "Default")
      (node (ref "R4") (pin "1") (pinfunction "1_1") (pintype "passive"))
      (node (ref "T2") (pin "1") (pinfunction "B_1") (pintype "passive"))
    )
    (net (code "70") (name "Net-(T2-C)") (class "Default")
      (node (ref "R3") (pin "1") (pinfunction "1_1") (pintype "passive"))
      (node (ref "T2") (pin "3") (pinfunction "C_3") (pintype "passive"))
    )
    (net (code "71") (name "Net-(T3-B)") (class "Default")
      (node (ref "R6") (pin "1") (pinfunction "1_1") (pintype "passive"))
      (node (ref "T3") (pin "1") (pinfunction "B_1") (pintype "passive"))
    )
    (net (code "72") (name "Net-(T3-C)") (class "Default")
      (node (ref "R5") (pin "1") (pinfunction "1_1") (pintype "passive"))
      (node (ref "T3") (pin "3") (pinfunction "C_3") (pintype "passive"))
    )
    (net (code "73") (name "Net-(T4-B)") (class "Default")
      (node (ref "R8") (pin "1") (pinfunction "1_1") (pintype "passive"))
      (node (ref "T4") (pin "1") (pinfunction "B_1") (pintype "passive"))
    )
    (net (code "74") (name "Net-(T4-C)") (class "Default")
      (node (ref "R7") (pin "1") (pinfunction "1_1") (pintype "passive"))
      (node (ref "T4") (pin "3") (pinfunction "C_3") (pintype "passive"))
    )
    (net (code "75") (name "Net-(T5-B)") (class "Default")
      (node (ref "R10") (pin "1") (pinfunction "1_1") (pintype "passive"))
      (node (ref "T5") (pin "1") (pinfunction "B_1") (pintype "passive"))
    )
    (net (code "76") (name "Net-(T5-C)") (class "Default")
      (node (ref "R9") (pin "1") (pinfunction "1_1") (pintype "passive"))
      (node (ref "T5") (pin "3") (pinfunction "C_3") (pintype "passive"))
    )
    (net (code "77") (name "Net-(T6-B)") (class "Default")
      (node (ref "R12") (pin "1") (pinfunction "1_1") (pintype "passive"))
      (node (ref "T6") (pin "1") (pinfunction "B_1") (pintype "passive"))
    )
    (net (code "78") (name "Net-(T6-C)") (class "Default")
      (node (ref "R11") (pin "1") (pinfunction "1_1") (pintype "passive"))
      (node (ref "T6") (pin "3") (pinfunction "C_3") (pintype "passive"))
    )
    (net (code "79") (name "Net-(T7-B)") (class "Default")
      (node (ref "R14") (pin "1") (pinfunction "1_1") (pintype "passive"))
      (node (ref "T7") (pin "1") (pinfunction "B_1") (pintype "passive"))
    )
    (net (code "80") (name "Net-(T7-C)") (class "Default")
      (node (ref "R13") (pin "1") (pinfunction "1_1") (pintype "passive"))
      (node (ref "T7") (pin "3") (pinfunction "C_3") (pintype "passive"))
    )
    (net (code "81") (name "Net-(T8-B)") (class "Default")
      (node (ref "R16") (pin "1") (pinfunction "1_1") (pintype "passive"))
      (node (ref "T8") (pin "1") (pinfunction "B_1") (pintype "passive"))
    )
    (net (code "82") (name "Net-(T8-C)") (class "Default")
      (node (ref "R15") (pin "1") (pinfunction "1_1") (pintype "passive"))
      (node (ref "T8") (pin "3") (pinfunction "C_3") (pintype "passive"))
    )
    (net (code "83") (name "Net-(T9-B)") (class "Default")
      (node (ref "R18") (pin "1") (pinfunction "1_1") (pintype "passive"))
      (node (ref "T9") (pin "1") (pinfunction "B_1") (pintype "passive"))
    )
    (net (code "84") (name "Net-(T9-C)") (class "Default")
      (node (ref "R17") (pin "1") (pinfunction "1_1") (pintype "passive"))
      (node (ref "T9") (pin "3") (pinfunction "C_3") (pintype "passive"))
    )
    (net (code "85") (name "Net-(T10-B)") (class "Default")
      (node (ref "R20") (pin "1") (pinfunction "1_1") (pintype "passive"))
      (node (ref "T10") (pin "1") (pinfunction "B_1") (pintype "passive"))
    )
    (net (code "86") (name "Net-(T10-C)") (class "Default")
      (node (ref "R19") (pin "1") (pinfunction "1_1") (pintype "passive"))
      (node (ref "T10") (pin "3") (pinfunction "C_3") (pintype "passive"))
    )
    (net (code "87") (name "Net-(T11-B)") (class "Default")
      (node (ref "R22") (pin "1") (pinfunction "1_1") (pintype "passive"))
      (node (ref "T11") (pin "1") (pinfunction "B_1") (pintype "passive"))
    )
    (net (code "88") (name "Net-(T11-C)") (class "Default")
      (node (ref "R21") (pin "1") (pinfunction "1_1") (pintype "passive"))
      (node (ref "T11") (pin "3") (pinfunction "C_3") (pintype "passive"))
    )
    (net (code "89") (name "Net-(T12-B)") (class "Default")
      (node (ref "R24") (pin "1") (pinfunction "1_1") (pintype "passive"))
      (node (ref "T12") (pin "1") (pinfunction "B_1") (pintype "passive"))
    )
    (net (code "90") (name "Net-(T12-C)") (class "Default")
      (node (ref "R23") (pin "1") (pinfunction "1_1") (pintype "passive"))
      (node (ref "T12") (pin "3") (pinfunction "C_3") (pintype "passive"))
    )
    (net (code "91") (name "Net-(T13-B)") (class "Default")
      (node (ref "R26") (pin "1") (pinfunction "1_1") (pintype "passive"))
      (node (ref "T13") (pin "1") (pinfunction "B_1") (pintype "passive"))
    )
    (net (code "92") (name "Net-(T13-C)") (class "Default")
      (node (ref "R25") (pin "1") (pinfunction "1_1") (pintype "passive"))
      (node (ref "T13") (pin "3") (pinfunction "C_3") (pintype "passive"))
    )
    (net (code "93") (name "Net-(T14-B)") (class "Default")
      (node (ref "R28") (pin "1") (pinfunction "1_1") (pintype "passive"))
      (node (ref "T14") (pin "1") (pinfunction "B_1") (pintype "passive"))
    )
    (net (code "94") (name "Net-(T14-C)") (class "Default")
      (node (ref "R27") (pin "1") (pinfunction "1_1") (pintype "passive"))
      (node (ref "T14") (pin "3") (pinfunction "C_3") (pintype "passive"))
    )
    (net (code "95") (name "Net-(T15-B)") (class "Default")
      (node (ref "R30") (pin "1") (pinfunction "1_1") (pintype "passive"))
      (node (ref "T15") (pin "1") (pinfunction "B_1") (pintype "passive"))
    )
    (net (code "96") (name "Net-(T15-C)") (class "Default")
      (node (ref "R29") (pin "1") (pinfunction "1_1") (pintype "passive"))
      (node (ref "T15") (pin "3") (pinfunction "C_3") (pintype "passive"))
    )
    (net (code "97") (name "Net-(T16-B)") (class "Default")
      (node (ref "R32") (pin "1") (pinfunction "1_1") (pintype "passive"))
      (node (ref "T16") (pin "1") (pinfunction "B_1") (pintype "passive"))
    )
    (net (code "98") (name "Net-(T16-C)") (class "Default")
      (node (ref "R31") (pin "1") (pinfunction "1_1") (pintype "passive"))
      (node (ref "T16") (pin "3") (pinfunction "C_3") (pintype "passive"))
    )
    (net (code "99") (name "Net-(T17-B)") (class "Default")
      (node (ref "R34") (pin "1") (pinfunction "1_1") (pintype "passive"))
      (node (ref "T17") (pin "1") (pinfunction "B_1") (pintype "passive"))
    )
    (net (code "100") (name "Net-(T17-C)") (class "Default")
      (node (ref "R33") (pin "1") (pinfunction "1_1") (pintype "passive"))
      (node (ref "T17") (pin "3") (pinfunction "C_3") (pintype "passive"))
    )
    (net (code "101") (name "Net-(T18-B)") (class "Default")
      (node (ref "R36") (pin "1") (pinfunction "1_1") (pintype "passive"))
      (node (ref "T18") (pin "1") (pinfunction "B_1") (pintype "passive"))
    )
    (net (code "102") (name "Net-(T18-C)") (class "Default")
      (node (ref "R35") (pin "1") (pinfunction "1_1") (pintype "passive"))
      (node (ref "T18") (pin "3") (pinfunction "C_3") (pintype "passive"))
    )
    (net (code "103") (name "Net-(T19-B)") (class "Default")
      (node (ref "R38") (pin "1") (pinfunction "1_1") (pintype "passive"))
      (node (ref "T19") (pin "1") (pinfunction "B_1") (pintype "passive"))
    )
    (net (code "104") (name "Net-(T19-C)") (class "Default")
      (node (ref "R37") (pin "1") (pinfunction "1_1") (pintype "passive"))
      (node (ref "T19") (pin "3") (pinfunction "C_3") (pintype "passive"))
    )
    (net (code "105") (name "Net-(T20-B)") (class "Default")
      (node (ref "R40") (pin "1") (pinfunction "1_1") (pintype "passive"))
      (node (ref "T20") (pin "1") (pinfunction "B_1") (pintype "passive"))
    )
    (net (code "106") (name "Net-(T20-C)") (class "Default")
      (node (ref "R39") (pin "1") (pinfunction "1_1") (pintype "passive"))
      (node (ref "T20") (pin "3") (pinfunction "C_3") (pintype "passive"))
    )
    (net (code "107") (name "Net-(T21-B)") (class "Default")
      (node (ref "R42") (pin "1") (pinfunction "1_1") (pintype "passive"))
      (node (ref "T21") (pin "1") (pinfunction "B_1") (pintype "passive"))
    )
    (net (code "108") (name "Net-(T21-C)") (class "Default")
      (node (ref "R41") (pin "1") (pinfunction "1_1") (pintype "passive"))
      (node (ref "T21") (pin "3") (pinfunction "C_3") (pintype "passive"))
    )
    (net (code "109") (name "Net-(T22-B)") (class "Default")
      (node (ref "R44") (pin "1") (pinfunction "1_1") (pintype "passive"))
      (node (ref "T22") (pin "1") (pinfunction "B_1") (pintype "passive"))
    )
    (net (code "110") (name "Net-(T22-C)") (class "Default")
      (node (ref "R43") (pin "1") (pinfunction "1_1") (pintype "passive"))
      (node (ref "T22") (pin "3") (pinfunction "C_3") (pintype "passive"))
    )
    (net (code "111") (name "Net-(T23-B)") (class "Default")
      (node (ref "R46") (pin "1") (pinfunction "1_1") (pintype "passive"))
      (node (ref "T23") (pin "1") (pinfunction "B_1") (pintype "passive"))
    )
    (net (code "112") (name "Net-(T23-C)") (class "Default")
      (node (ref "R45") (pin "1") (pinfunction "1_1") (pintype "passive"))
      (node (ref "T23") (pin "3") (pinfunction "C_3") (pintype "passive"))
    )
    (net (code "113") (name "Net-(T24-B)") (class "Default")
      (node (ref "R48") (pin "1") (pinfunction "1_1") (pintype "passive"))
      (node (ref "T24") (pin "1") (pinfunction "B_1") (pintype "passive"))
    )
    (net (code "114") (name "Net-(T24-C)") (class "Default")
      (node (ref "R47") (pin "1") (pinfunction "1_1") (pintype "passive"))
      (node (ref "T24") (pin "3") (pinfunction "C_3") (pintype "passive"))
    )
    (net (code "115") (name "Net-(T25-B)") (class "Default")
      (node (ref "R50") (pin "1") (pinfunction "1_1") (pintype "passive"))
      (node (ref "T25") (pin "1") (pinfunction "B_1") (pintype "passive"))
    )
    (net (code "116") (name "Net-(T25-C)") (class "Default")
      (node (ref "R49") (pin "1") (pinfunction "1_1") (pintype "passive"))
      (node (ref "T25") (pin "3") (pinfunction "C_3") (pintype "passive"))
    )
    (net (code "117") (name "Net-(T26-B)") (class "Default")
      (node (ref "R52") (pin "1") (pinfunction "1_1") (pintype "passive"))
      (node (ref "T26") (pin "1") (pinfunction "B_1") (pintype "passive"))
    )
    (net (code "118") (name "Net-(T26-C)") (class "Default")
      (node (ref "R51") (pin "1") (pinfunction "1_1") (pintype "passive"))
      (node (ref "T26") (pin "3") (pinfunction "C_3") (pintype "passive"))
    )
    (net (code "119") (name "Net-(T27-B)") (class "Default")
      (node (ref "R54") (pin "1") (pinfunction "1_1") (pintype "passive"))
      (node (ref "T27") (pin "1") (pinfunction "B_1") (pintype "passive"))
    )
    (net (code "120") (name "Net-(T27-C)") (class "Default")
      (node (ref "R53") (pin "1") (pinfunction "1_1") (pintype "passive"))
      (node (ref "T27") (pin "3") (pinfunction "C_3") (pintype "passive"))
    )
    (net (code "121") (name "Net-(T28-B)") (class "Default")
      (node (ref "R56") (pin "1") (pinfunction "1_1") (pintype "passive"))
      (node (ref "T28") (pin "1") (pinfunction "B_1") (pintype "passive"))
    )
    (net (code "122") (name "Net-(T28-C)") (class "Default")
      (node (ref "R55") (pin "1") (pinfunction "1_1") (pintype "passive"))
      (node (ref "T28") (pin "3") (pinfunction "C_3") (pintype "passive"))
    )
    (net (code "123") (name "Net-(T29-B)") (class "Default")
      (node (ref "R58") (pin "1") (pinfunction "1_1") (pintype "passive"))
      (node (ref "T29") (pin "1") (pinfunction "B_1") (pintype "passive"))
    )
    (net (code "124") (name "Net-(T29-C)") (class "Default")
      (node (ref "R57") (pin "1") (pinfunction "1_1") (pintype "passive"))
      (node (ref "T29") (pin "3") (pinfunction "C_3") (pintype "passive"))
    )
    (net (code "125") (name "Net-(T30-B)") (class "Default")
      (node (ref "R60") (pin "1") (pinfunction "1_1") (pintype "passive"))
      (node (ref "T30") (pin "1") (pinfunction "B_1") (pintype "passive"))
    )
    (net (code "126") (name "Net-(T30-C)") (class "Default")
      (node (ref "R59") (pin "1") (pinfunction "1_1") (pintype "passive"))
      (node (ref "T30") (pin "3") (pinfunction "C_3") (pintype "passive"))
    )
  )
)
